# capacitive_switch.net
KiCad netlist of a schematic drawn in EAGLE
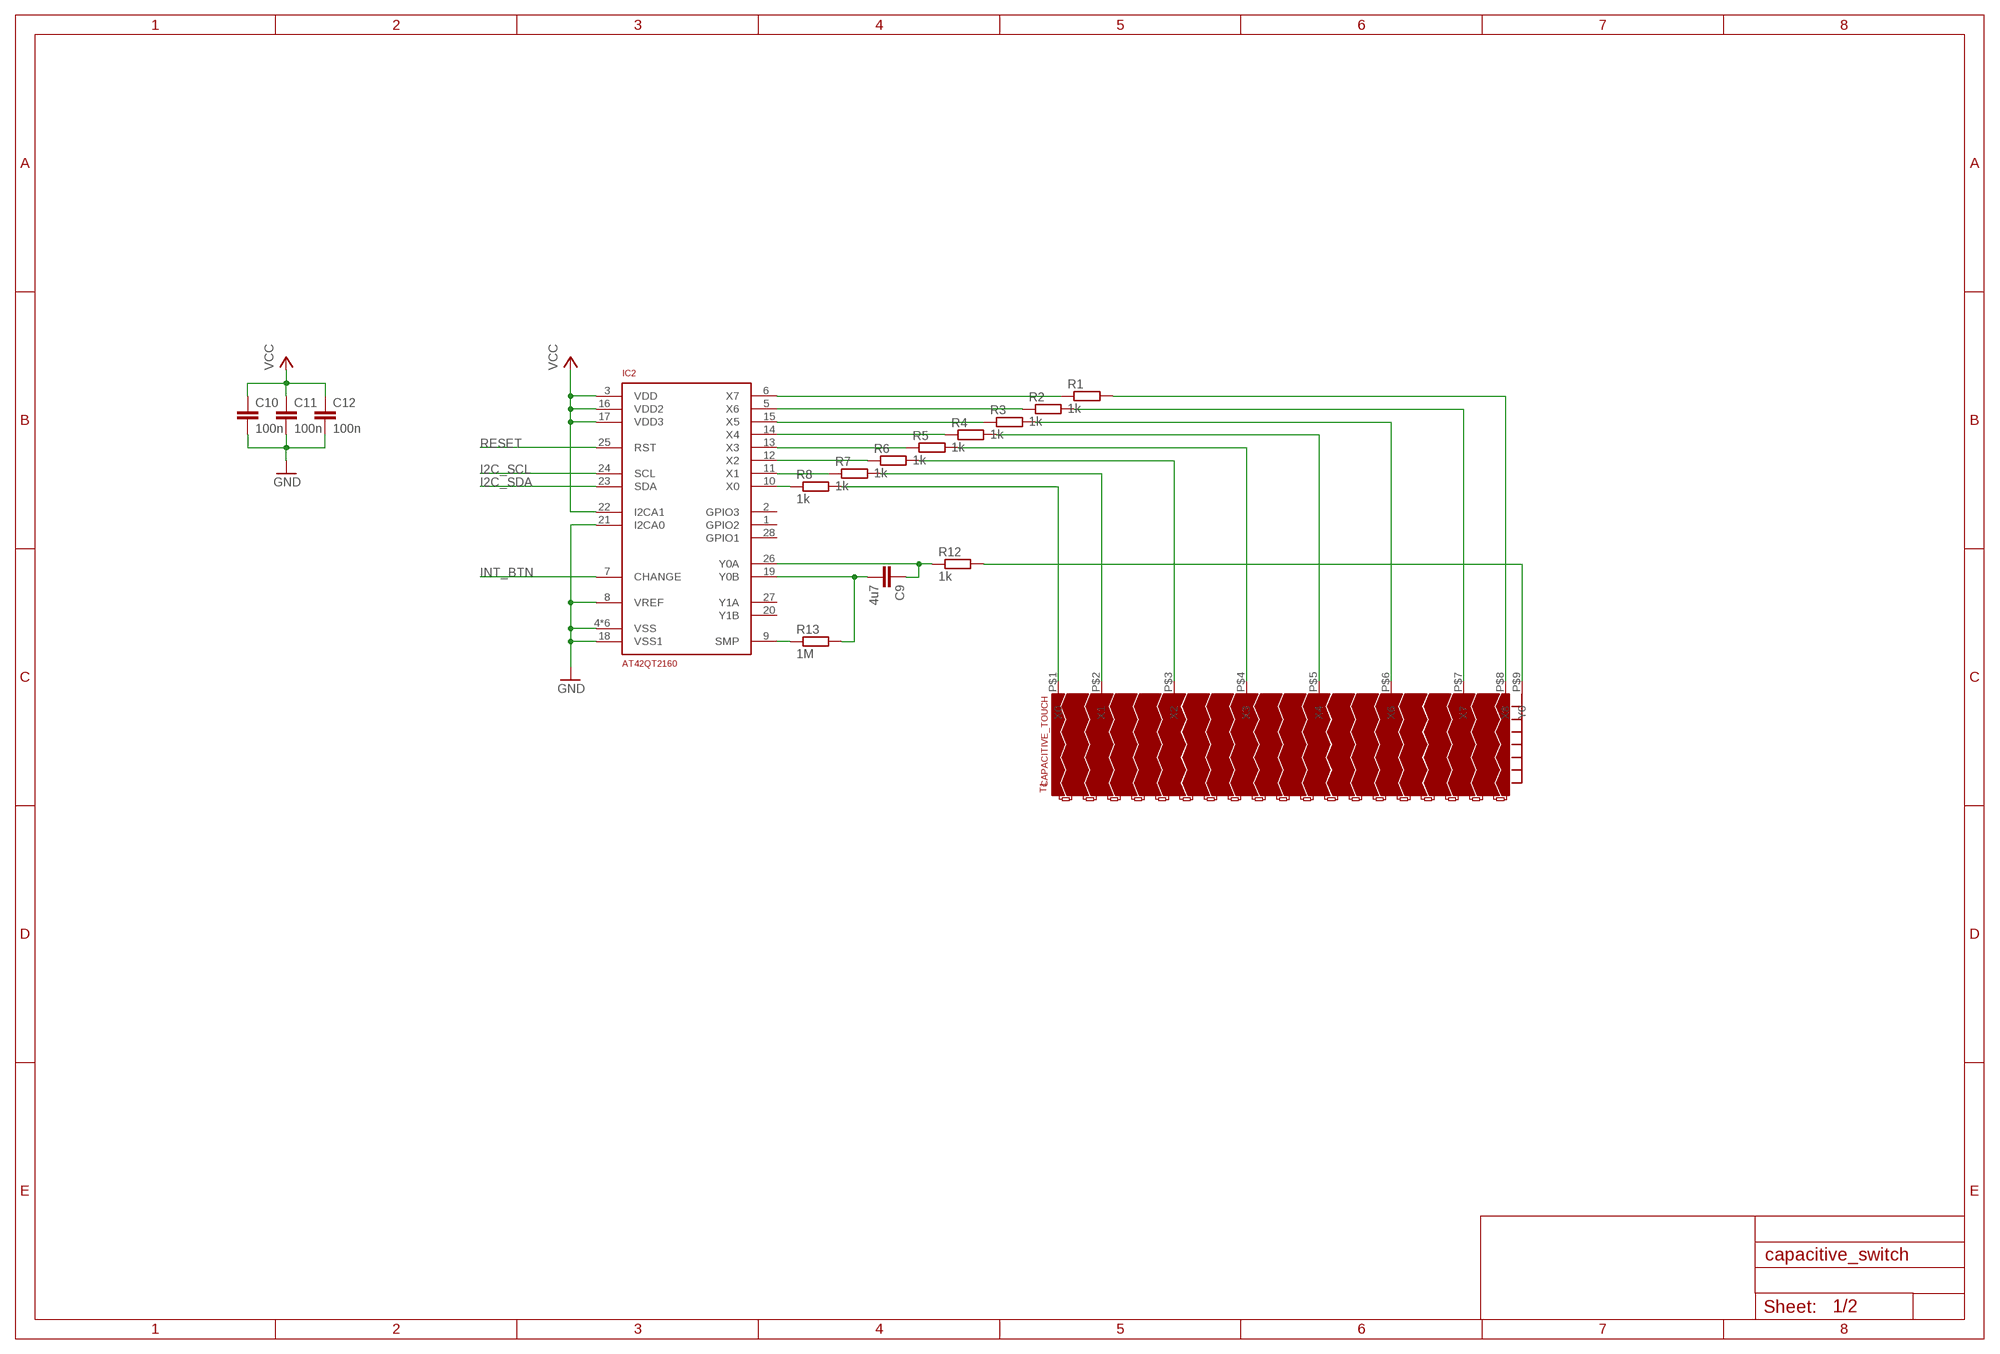
[diagram p0: schematic, sheet 1]
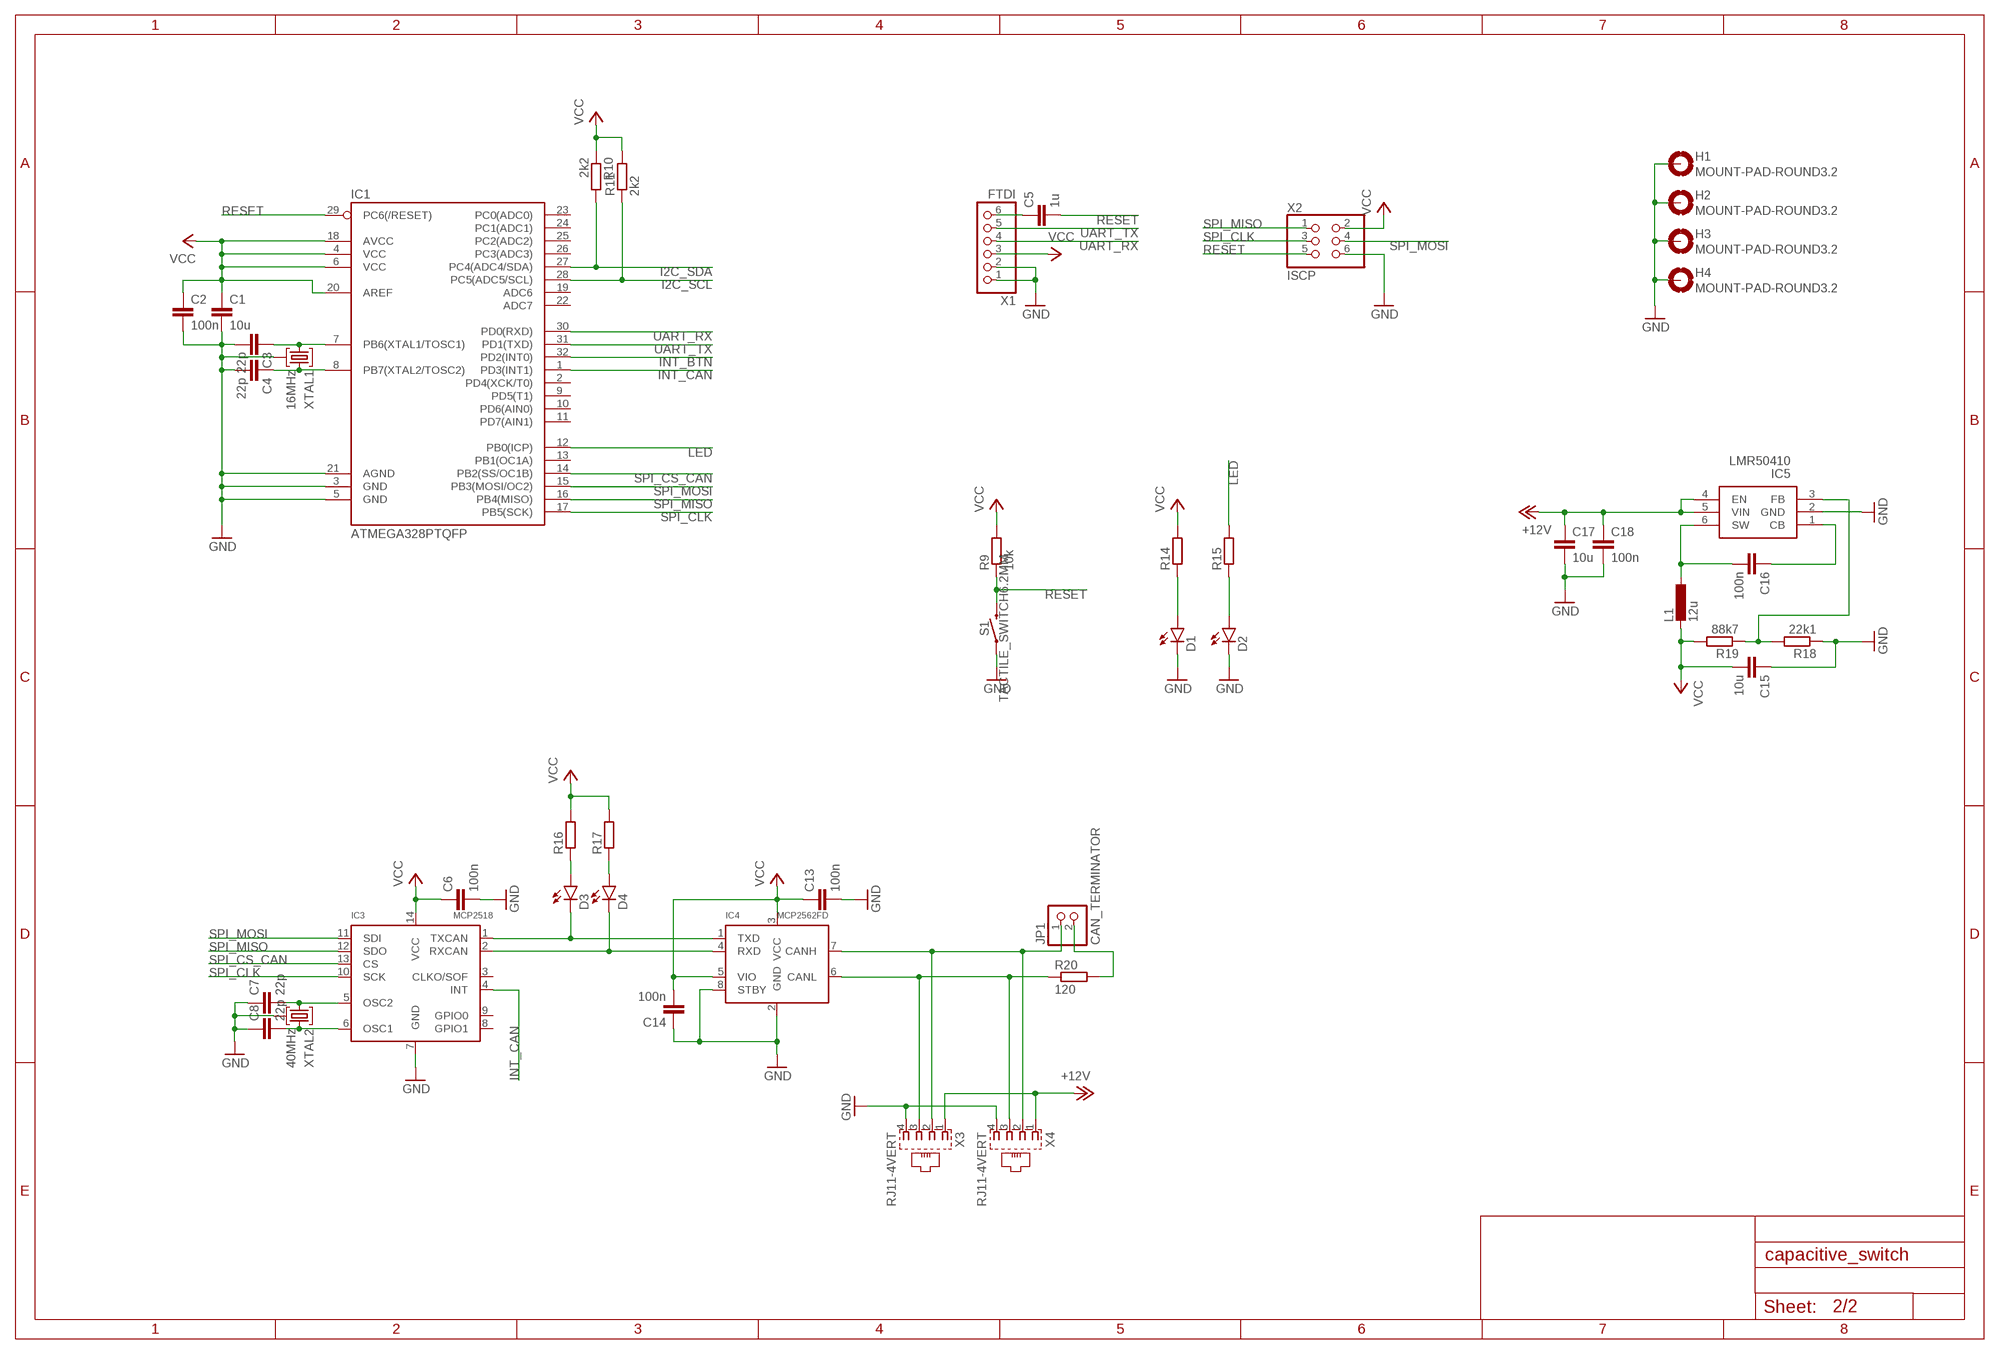
[diagram p1: schematic, sheet 2]

(export (version "E")
  (design (tool "Eeschema 10.0.6"))
  (components
    (comp (ref "C1")
      (value "10u")
      (footprint "eagle-import:C1206")
      (libsource (lib "eagle-import") (part "CAPACITOR1206"))
    )
    (comp (ref "C2")
      (value "100n")
      (footprint "eagle-import:C0805")
      (libsource (lib "eagle-import") (part "CAPACITOR0805"))
    )
    (comp (ref "C3")
      (value "22p")
      (footprint "eagle-import:C0805")
      (libsource (lib "eagle-import") (part "CAPACITOR0805"))
    )
    (comp (ref "C4")
      (value "22p")
      (footprint "eagle-import:C0805")
      (libsource (lib "eagle-import") (part "CAPACITOR0805"))
    )
    (comp (ref "C5")
      (value "1u")
      (footprint "eagle-import:C0805")
      (libsource (lib "eagle-import") (part "CAPACITOR0805"))
    )
    (comp (ref "C6")
      (value "100n")
      (footprint "eagle-import:C0805")
      (libsource (lib "eagle-import") (part "CAPACITOR0805"))
    )
    (comp (ref "C7")
      (value "22p")
      (footprint "eagle-import:C0805")
      (libsource (lib "eagle-import") (part "CAPACITOR0805"))
    )
    (comp (ref "C8")
      (value "22p")
      (footprint "eagle-import:C0805")
      (libsource (lib "eagle-import") (part "CAPACITOR0805"))
    )
    (comp (ref "C13")
      (value "100n")
      (footprint "eagle-import:C0805")
      (libsource (lib "eagle-import") (part "CAPACITOR0805"))
    )
    (comp (ref "C14")
      (value "100n")
      (footprint "eagle-import:C0805")
      (libsource (lib "eagle-import") (part "CAPACITOR0805"))
    )
    (comp (ref "C15")
      (value "10u")
      (footprint "eagle-import:C1206")
      (libsource (lib "eagle-import") (part "CAPACITOR1206"))
    )
    (comp (ref "C16")
      (value "100n")
      (footprint "eagle-import:C0805")
      (libsource (lib "eagle-import") (part "CAPACITOR0805"))
    )
    (comp (ref "C17")
      (value "10u")
      (footprint "eagle-import:C1206")
      (libsource (lib "eagle-import") (part "CAPACITOR1206"))
    )
    (comp (ref "C18")
      (value "100n")
      (footprint "eagle-import:C0805")
      (libsource (lib "eagle-import") (part "CAPACITOR0805"))
    )
    (comp (ref "D1")
      (value "LED1206")
      (footprint "eagle-import:CHIPLED_1206")
      (libsource (lib "eagle-import") (part "LED1206"))
    )
    (comp (ref "D2")
      (value "LED1206")
      (footprint "eagle-import:CHIPLED_1206")
      (libsource (lib "eagle-import") (part "LED1206"))
    )
    (comp (ref "D3")
      (value "LED1206")
      (footprint "eagle-import:CHIPLED_1206")
      (libsource (lib "eagle-import") (part "LED1206"))
    )
    (comp (ref "D4")
      (value "LED1206")
      (footprint "eagle-import:CHIPLED_1206")
      (libsource (lib "eagle-import") (part "LED1206"))
    )
    (comp (ref "H1")
      (value "MOUNT-PAD-ROUND3.2")
      (footprint "eagle-import:3,2-PAD")
      (libsource (lib "eagle-import") (part "MOUNT-PAD-ROUND3.2"))
    )
    (comp (ref "H2")
      (value "MOUNT-PAD-ROUND3.2")
      (footprint "eagle-import:3,2-PAD")
      (libsource (lib "eagle-import") (part "MOUNT-PAD-ROUND3.2"))
    )
    (comp (ref "H3")
      (value "MOUNT-PAD-ROUND3.2")
      (footprint "eagle-import:3,2-PAD")
      (libsource (lib "eagle-import") (part "MOUNT-PAD-ROUND3.2"))
    )
    (comp (ref "H4")
      (value "MOUNT-PAD-ROUND3.2")
      (footprint "eagle-import:3,2-PAD")
      (libsource (lib "eagle-import") (part "MOUNT-PAD-ROUND3.2"))
    )
    (comp (ref "IC1")
      (value "ATMEGA328PTQFP")
      (footprint "eagle-import:TQFP32_0.8MM_7X7MM")
      (libsource (lib "eagle-import") (part "ATMEGA328PTQFP"))
    )
    (comp (ref "IC3")
      (value "MCP2518")
      (footprint "eagle-import:SO14")
      (libsource (lib "eagle-import") (part "MCP2518FDSO14"))
    )
    (comp (ref "IC4")
      (value "MCP2562FD")
      (footprint "eagle-import:SO08")
      (libsource (lib "eagle-import") (part "MCP2562FDSO08"))
    )
    (comp (ref "IC5")
      (value "LMR50410")
      (footprint "eagle-import:SOT23-6")
      (libsource (lib "eagle-import") (part "LMR50410"))
    )
    (comp (ref "JP1")
      (value "CAN_TERMINATOR")
      (footprint "eagle-import:1X02")
      (libsource (lib "eagle-import") (part "PINHD-1X2"))
    )
    (comp (ref "L1")
      (value "12u")
      (footprint "eagle-import:L_7.3MM")
      (libsource (lib "eagle-import") (part "INDUCTOR7.3MM"))
    )
    (comp (ref "R9")
      (value "10k")
      (footprint "eagle-import:R0805")
      (libsource (lib "eagle-import") (part "RESISTOR0805"))
    )
    (comp (ref "R10")
      (value "2k2")
      (footprint "eagle-import:R0805")
      (libsource (lib "eagle-import") (part "RESISTOR0805"))
    )
    (comp (ref "R11")
      (value "2k2")
      (footprint "eagle-import:R0805")
      (libsource (lib "eagle-import") (part "RESISTOR0805"))
    )
    (comp (ref "R14")
      (value "RESISTOR0805")
      (footprint "eagle-import:R0805")
      (libsource (lib "eagle-import") (part "RESISTOR0805"))
    )
    (comp (ref "R15")
      (value "RESISTOR0805")
      (footprint "eagle-import:R0805")
      (libsource (lib "eagle-import") (part "RESISTOR0805"))
    )
    (comp (ref "R16")
      (value "RESISTOR0805")
      (footprint "eagle-import:R0805")
      (libsource (lib "eagle-import") (part "RESISTOR0805"))
    )
    (comp (ref "R17")
      (value "RESISTOR0805")
      (footprint "eagle-import:R0805")
      (libsource (lib "eagle-import") (part "RESISTOR0805"))
    )
    (comp (ref "R18")
      (value "22k1")
      (footprint "eagle-import:R0805")
      (libsource (lib "eagle-import") (part "RESISTOR0805"))
    )
    (comp (ref "R19")
      (value "88k7")
      (footprint "eagle-import:R0805")
      (libsource (lib "eagle-import") (part "RESISTOR0805"))
    )
    (comp (ref "R20")
      (value "120")
      (footprint "eagle-import:R0805")
      (libsource (lib "eagle-import") (part "RESISTOR0805"))
    )
    (comp (ref "S1")
      (value "TACTILE_SWITCH6.2MM")
      (footprint "eagle-import:TACTILE_SWITCH_SMD_6.2MM")
      (libsource (lib "eagle-import") (part "TACTILE_SWITCH6.2MM"))
    )
    (comp (ref "X1")
      (value "FTDI")
      (footprint "eagle-import:1X06")
      (libsource (lib "eagle-import") (part "PINHD-1X6"))
    )
    (comp (ref "X2")
      (value "ISCP")
      (footprint "eagle-import:2X03")
      (libsource (lib "eagle-import") (part "PINHD-2X3"))
    )
    (comp (ref "X3")
      (value "RJ11-4VERT")
      (footprint "eagle-import:RJ11-4_VERT")
      (libsource (lib "eagle-import") (part "RJ11-4VERT"))
    )
    (comp (ref "X4")
      (value "RJ11-4VERT")
      (footprint "eagle-import:RJ11-4_VERT")
      (libsource (lib "eagle-import") (part "RJ11-4VERT"))
    )
    (comp (ref "XTAL1")
      (value "16MHz")
      (footprint "eagle-import:XTAL_5.0X3.2_4")
      (libsource (lib "eagle-import") (part "CRYSTAL_GND5X3.2"))
    )
    (comp (ref "XTAL2")
      (value "40MHz")
      (footprint "eagle-import:XTAL_5.0X3.2_4")
      (libsource (lib "eagle-import") (part "CRYSTAL_GND5X3.2"))
    )
    (comp (ref "C9")
      (value "4u7")
      (footprint "eagle-import:C0805")
      (libsource (lib "eagle-import") (part "CAPACITOR0805"))
    )
    (comp (ref "C10")
      (value "100n")
      (footprint "eagle-import:C0805")
      (libsource (lib "eagle-import") (part "CAPACITOR0805"))
    )
    (comp (ref "C11")
      (value "100n")
      (footprint "eagle-import:C0805")
      (libsource (lib "eagle-import") (part "CAPACITOR0805"))
    )
    (comp (ref "C12")
      (value "100n")
      (footprint "eagle-import:C0805")
      (libsource (lib "eagle-import") (part "CAPACITOR0805"))
    )
    (comp (ref "IC2")
      (value "AT42QT2160")
      (footprint "eagle-import:QFN28_0.45MM_4X4MM")
      (libsource (lib "eagle-import") (part "AT42QT2160"))
    )
    (comp (ref "R1")
      (value "1k")
      (footprint "eagle-import:R0805")
      (libsource (lib "eagle-import") (part "RESISTOR0805"))
    )
    (comp (ref "R2")
      (value "1k")
      (footprint "eagle-import:R0805")
      (libsource (lib "eagle-import") (part "RESISTOR0805"))
    )
    (comp (ref "R3")
      (value "1k")
      (footprint "eagle-import:R0805")
      (libsource (lib "eagle-import") (part "RESISTOR0805"))
    )
    (comp (ref "R4")
      (value "1k")
      (footprint "eagle-import:R0805")
      (libsource (lib "eagle-import") (part "RESISTOR0805"))
    )
    (comp (ref "R5")
      (value "1k")
      (footprint "eagle-import:R0805")
      (libsource (lib "eagle-import") (part "RESISTOR0805"))
    )
    (comp (ref "R6")
      (value "1k")
      (footprint "eagle-import:R0805")
      (libsource (lib "eagle-import") (part "RESISTOR0805"))
    )
    (comp (ref "R7")
      (value "1k")
      (footprint "eagle-import:R0805")
      (libsource (lib "eagle-import") (part "RESISTOR0805"))
    )
    (comp (ref "R8")
      (value "1k")
      (footprint "eagle-import:R0805")
      (libsource (lib "eagle-import") (part "RESISTOR0805"))
    )
    (comp (ref "R12")
      (value "1k")
      (footprint "eagle-import:R0805")
      (libsource (lib "eagle-import") (part "RESISTOR0805"))
    )
    (comp (ref "R13")
      (value "1M")
      (footprint "eagle-import:R0805")
      (libsource (lib "eagle-import") (part "RESISTOR0805"))
    )
    (comp (ref "T1")
      (value "CAPACITIVE_TOUCH")
      (footprint "eagle-import:90X20_CAPACITIVE_TOUCH")
      (libsource (lib "eagle-import") (part "CAPACITIVE_TOUCH"))
    )
  )
  (nets
    (net (code "1") (name "+12V") (class "Default")
      (node (ref "C17") (pin "1") (pinfunction "1_1") (pintype "passive"))
      (node (ref "C18") (pin "1") (pinfunction "1_1") (pintype "passive"))
      (node (ref "IC5") (pin "4") (pinfunction "EN_4") (pintype "bidirectional"))
      (node (ref "IC5") (pin "5") (pinfunction "VIN_5") (pintype "bidirectional"))
      (node (ref "X3") (pin "1") (pinfunction "1_1") (pintype "passive"))
      (node (ref "X4") (pin "1") (pinfunction "1_1") (pintype "passive"))
    )
    (net (code "2") (name "GND") (class "Default")
      (node (ref "C1") (pin "2") (pinfunction "2_2") (pintype "passive"))
      (node (ref "C10") (pin "2") (pinfunction "2_2") (pintype "passive"))
      (node (ref "C11") (pin "2") (pinfunction "2_2") (pintype "passive"))
      (node (ref "C12") (pin "2") (pinfunction "2_2") (pintype "passive"))
      (node (ref "C13") (pin "2") (pinfunction "2_2") (pintype "passive"))
      (node (ref "C14") (pin "1") (pinfunction "1_1") (pintype "passive"))
      (node (ref "C15") (pin "1") (pinfunction "1_1") (pintype "passive"))
      (node (ref "C17") (pin "2") (pinfunction "2_2") (pintype "passive"))
      (node (ref "C18") (pin "2") (pinfunction "2_2") (pintype "passive"))
      (node (ref "C2") (pin "2") (pinfunction "2_2") (pintype "passive"))
      (node (ref "C3") (pin "2") (pinfunction "2_2") (pintype "passive"))
      (node (ref "C4") (pin "2") (pinfunction "2_2") (pintype "passive"))
      (node (ref "C6") (pin "2") (pinfunction "2_2") (pintype "passive"))
      (node (ref "C7") (pin "1") (pinfunction "1_1") (pintype "passive"))
      (node (ref "C8") (pin "1") (pinfunction "1_1") (pintype "passive"))
      (node (ref "D1") (pin "C") (pinfunction "C_C") (pintype "passive"))
      (node (ref "D2") (pin "C") (pinfunction "C_C") (pintype "passive"))
      (node (ref "H1") (pin "B3,2") (pinfunction "MOUNT_B3,2") (pintype "passive"))
      (node (ref "H1") (pin "P$1") (pinfunction "MOUNT_P$1") (pintype "passive"))
      (node (ref "H1") (pin "P$2") (pinfunction "MOUNT_P$2") (pintype "passive"))
      (node (ref "H1") (pin "P$3") (pinfunction "MOUNT_P$3") (pintype "passive"))
      (node (ref "H1") (pin "P$4") (pinfunction "MOUNT_P$4") (pintype "passive"))
      (node (ref "H1") (pin "P$5") (pinfunction "MOUNT_P$5") (pintype "passive"))
      (node (ref "H1") (pin "P$6") (pinfunction "MOUNT_P$6") (pintype "passive"))
      (node (ref "H1") (pin "P$7") (pinfunction "MOUNT_P$7") (pintype "passive"))
      (node (ref "H1") (pin "P$8") (pinfunction "MOUNT_P$8") (pintype "passive"))
      (node (ref "H2") (pin "B3,2") (pinfunction "MOUNT_B3,2") (pintype "passive"))
      (node (ref "H2") (pin "P$1") (pinfunction "MOUNT_P$1") (pintype "passive"))
      (node (ref "H2") (pin "P$2") (pinfunction "MOUNT_P$2") (pintype "passive"))
      (node (ref "H2") (pin "P$3") (pinfunction "MOUNT_P$3") (pintype "passive"))
      (node (ref "H2") (pin "P$4") (pinfunction "MOUNT_P$4") (pintype "passive"))
      (node (ref "H2") (pin "P$5") (pinfunction "MOUNT_P$5") (pintype "passive"))
      (node (ref "H2") (pin "P$6") (pinfunction "MOUNT_P$6") (pintype "passive"))
      (node (ref "H2") (pin "P$7") (pinfunction "MOUNT_P$7") (pintype "passive"))
      (node (ref "H2") (pin "P$8") (pinfunction "MOUNT_P$8") (pintype "passive"))
      (node (ref "H3") (pin "B3,2") (pinfunction "MOUNT_B3,2") (pintype "passive"))
      (node (ref "H3") (pin "P$1") (pinfunction "MOUNT_P$1") (pintype "passive"))
      (node (ref "H3") (pin "P$2") (pinfunction "MOUNT_P$2") (pintype "passive"))
      (node (ref "H3") (pin "P$3") (pinfunction "MOUNT_P$3") (pintype "passive"))
      (node (ref "H3") (pin "P$4") (pinfunction "MOUNT_P$4") (pintype "passive"))
      (node (ref "H3") (pin "P$5") (pinfunction "MOUNT_P$5") (pintype "passive"))
      (node (ref "H3") (pin "P$6") (pinfunction "MOUNT_P$6") (pintype "passive"))
      (node (ref "H3") (pin "P$7") (pinfunction "MOUNT_P$7") (pintype "passive"))
      (node (ref "H3") (pin "P$8") (pinfunction "MOUNT_P$8") (pintype "passive"))
      (node (ref "H4") (pin "B3,2") (pinfunction "MOUNT_B3,2") (pintype "passive"))
      (node (ref "H4") (pin "P$1") (pinfunction "MOUNT_P$1") (pintype "passive"))
      (node (ref "H4") (pin "P$2") (pinfunction "MOUNT_P$2") (pintype "passive"))
      (node (ref "H4") (pin "P$3") (pinfunction "MOUNT_P$3") (pintype "passive"))
      (node (ref "H4") (pin "P$4") (pinfunction "MOUNT_P$4") (pintype "passive"))
      (node (ref "H4") (pin "P$5") (pinfunction "MOUNT_P$5") (pintype "passive"))
      (node (ref "H4") (pin "P$6") (pinfunction "MOUNT_P$6") (pintype "passive"))
      (node (ref "H4") (pin "P$7") (pinfunction "MOUNT_P$7") (pintype "passive"))
      (node (ref "H4") (pin "P$8") (pinfunction "MOUNT_P$8") (pintype "passive"))
      (node (ref "IC1") (pin "21") (pinfunction "AGND_21") (pintype "bidirectional"))
      (node (ref "IC1") (pin "3") (pinfunction "GND_3") (pintype "bidirectional"))
      (node (ref "IC1") (pin "5") (pinfunction "GND_5") (pintype "bidirectional"))
      (node (ref "IC2") (pin "18") (pinfunction "VSS1_18") (pintype "bidirectional"))
      (node (ref "IC2") (pin "21") (pinfunction "I2CA0_21") (pintype "bidirectional"))
      (node (ref "IC2") (pin "29") (pinfunction "VSS_29") (pintype "bidirectional"))
      (node (ref "IC2") (pin "4") (pinfunction "VSS_4") (pintype "bidirectional"))
      (node (ref "IC2") (pin "8") (pinfunction "VREF_8") (pintype "bidirectional"))
      (node (ref "IC2") (pin "P$1") (pinfunction "VSS_P$1") (pintype "bidirectional"))
      (node (ref "IC2") (pin "P$2") (pinfunction "VSS_P$2") (pintype "bidirectional"))
      (node (ref "IC2") (pin "P$3") (pinfunction "VSS_P$3") (pintype "bidirectional"))
      (node (ref "IC2") (pin "P$4") (pinfunction "VSS_P$4") (pintype "bidirectional"))
      (node (ref "IC3") (pin "7") (pinfunction "GND_7") (pintype "bidirectional"))
      (node (ref "IC4") (pin "2") (pinfunction "GND_2") (pintype "bidirectional"))
      (node (ref "IC4") (pin "8") (pinfunction "STBY_8") (pintype "bidirectional"))
      (node (ref "IC5") (pin "2") (pinfunction "GND_2") (pintype "bidirectional"))
      (node (ref "R18") (pin "1") (pinfunction "1_1") (pintype "passive"))
      (node (ref "S1") (pin "A1") (pinfunction "1_A1") (pintype "passive"))
      (node (ref "S1") (pin "A2") (pinfunction "1_A2") (pintype "passive"))
      (node (ref "X1") (pin "1") (pinfunction "1_1") (pintype "passive"))
      (node (ref "X1") (pin "2") (pinfunction "2_2") (pintype "passive"))
      (node (ref "X2") (pin "6") (pinfunction "6_6") (pintype "passive"))
      (node (ref "X3") (pin "4") (pinfunction "4_4") (pintype "passive"))
      (node (ref "X4") (pin "4") (pinfunction "4_4") (pintype "passive"))
      (node (ref "XTAL1") (pin "2") (pinfunction "2_2") (pintype "passive"))
      (node (ref "XTAL1") (pin "4") (pinfunction "2_4") (pintype "passive"))
      (node (ref "XTAL2") (pin "2") (pinfunction "2_2") (pintype "passive"))
      (node (ref "XTAL2") (pin "4") (pinfunction "2_4") (pintype "passive"))
    )
    (net (code "3") (name "I2C_SCL") (class "Default")
      (node (ref "IC1") (pin "28") (pinfunction "PC5(ADC5/SCL)_28") (pintype "bidirectional"))
      (node (ref "IC2") (pin "24") (pinfunction "SCL_24") (pintype "bidirectional"))
      (node (ref "R11") (pin "1") (pinfunction "1_1") (pintype "passive"))
    )
    (net (code "4") (name "I2C_SDA") (class "Default")
      (node (ref "IC1") (pin "27") (pinfunction "PC4(ADC4/SDA)_27") (pintype "bidirectional"))
      (node (ref "IC2") (pin "23") (pinfunction "SDA_23") (pintype "bidirectional"))
      (node (ref "R10") (pin "2") (pinfunction "2_2") (pintype "passive"))
    )
    (net (code "5") (name "INT_BTN") (class "Default")
      (node (ref "IC1") (pin "32") (pinfunction "PD2(INT0)_32") (pintype "bidirectional"))
      (node (ref "IC2") (pin "7") (pinfunction "CHANGE_7") (pintype "bidirectional"))
    )
    (net (code "6") (name "INT_CAN") (class "Default")
      (node (ref "IC1") (pin "1") (pinfunction "PD3(INT1)_1") (pintype "bidirectional"))
      (node (ref "IC3") (pin "4") (pinfunction "INT_4") (pintype "bidirectional"))
    )
    (net (code "7") (name "LED") (class "Default")
      (node (ref "IC1") (pin "12") (pinfunction "PB0(ICP)_12") (pintype "bidirectional"))
      (node (ref "R15") (pin "2") (pinfunction "2_2") (pintype "passive"))
    )
    (net (code "8") (name "Net-(C5-Pad1)") (class "Default")
      (node (ref "C5") (pin "1") (pinfunction "1_1") (pintype "passive"))
      (node (ref "X1") (pin "6") (pinfunction "6_6") (pintype "passive"))
    )
    (net (code "9") (name "Net-(D1-PadA)") (class "Default")
      (node (ref "D1") (pin "A") (pinfunction "A_A") (pintype "passive"))
      (node (ref "R14") (pin "1") (pinfunction "1_1") (pintype "passive"))
    )
    (net (code "10") (name "Net-(D2-PadA)") (class "Default")
      (node (ref "D2") (pin "A") (pinfunction "A_A") (pintype "passive"))
      (node (ref "R15") (pin "1") (pinfunction "1_1") (pintype "passive"))
    )
    (net (code "11") (name "Net-(D3-PadA)") (class "Default")
      (node (ref "D3") (pin "A") (pinfunction "A_A") (pintype "passive"))
      (node (ref "R16") (pin "1") (pinfunction "1_1") (pintype "passive"))
    )
    (net (code "12") (name "Net-(D4-PadA)") (class "Default")
      (node (ref "D4") (pin "A") (pinfunction "A_A") (pintype "passive"))
      (node (ref "R17") (pin "1") (pinfunction "1_1") (pintype "passive"))
    )
    (net (code "13") (name "Net-(IC1-PB6(XTAL1{slash}TOSC1))") (class "Default")
      (node (ref "C3") (pin "1") (pinfunction "1_1") (pintype "passive"))
      (node (ref "IC1") (pin "7") (pinfunction "PB6(XTAL1/TOSC1)_7") (pintype "bidirectional"))
      (node (ref "XTAL1") (pin "1") (pinfunction "1_1") (pintype "passive"))
    )
    (net (code "14") (name "Net-(IC1-PB7(XTAL2{slash}TOSC2))") (class "Default")
      (node (ref "C4") (pin "1") (pinfunction "1_1") (pintype "passive"))
      (node (ref "IC1") (pin "8") (pinfunction "PB7(XTAL2/TOSC2)_8") (pintype "bidirectional"))
      (node (ref "XTAL1") (pin "3") (pinfunction "3_3") (pintype "passive"))
    )
    (net (code "15") (name "Net-(IC2-SMP)") (class "Default")
      (node (ref "IC2") (pin "9") (pinfunction "SMP_9") (pintype "bidirectional"))
      (node (ref "R13") (pin "1") (pinfunction "1_1") (pintype "passive"))
    )
    (net (code "16") (name "Net-(IC2-X0)") (class "Default")
      (node (ref "IC2") (pin "10") (pinfunction "X0_10") (pintype "bidirectional"))
      (node (ref "R8") (pin "1") (pinfunction "1_1") (pintype "passive"))
    )
    (net (code "17") (name "Net-(IC2-X1)") (class "Default")
      (node (ref "IC2") (pin "11") (pinfunction "X1_11") (pintype "bidirectional"))
      (node (ref "R7") (pin "1") (pinfunction "1_1") (pintype "passive"))
    )
    (net (code "18") (name "Net-(IC2-X2)") (class "Default")
      (node (ref "IC2") (pin "12") (pinfunction "X2_12") (pintype "bidirectional"))
      (node (ref "R6") (pin "1") (pinfunction "1_1") (pintype "passive"))
    )
    (net (code "19") (name "Net-(IC2-X3)") (class "Default")
      (node (ref "IC2") (pin "13") (pinfunction "X3_13") (pintype "bidirectional"))
      (node (ref "R5") (pin "1") (pinfunction "1_1") (pintype "passive"))
    )
    (net (code "20") (name "Net-(IC2-X4)") (class "Default")
      (node (ref "IC2") (pin "14") (pinfunction "X4_14") (pintype "bidirectional"))
      (node (ref "R4") (pin "1") (pinfunction "1_1") (pintype "passive"))
    )
    (net (code "21") (name "Net-(IC2-X5)") (class "Default")
      (node (ref "IC2") (pin "15") (pinfunction "X5_15") (pintype "bidirectional"))
      (node (ref "R3") (pin "1") (pinfunction "1_1") (pintype "passive"))
    )
    (net (code "22") (name "Net-(IC2-X6)") (class "Default")
      (node (ref "IC2") (pin "5") (pinfunction "X6_5") (pintype "bidirectional"))
      (node (ref "R2") (pin "1") (pinfunction "1_1") (pintype "passive"))
    )
    (net (code "23") (name "Net-(IC2-X7)") (class "Default")
      (node (ref "IC2") (pin "6") (pinfunction "X7_6") (pintype "bidirectional"))
      (node (ref "R1") (pin "1") (pinfunction "1_1") (pintype "passive"))
    )
    (net (code "24") (name "Net-(IC2-Y0A)") (class "Default")
      (node (ref "C9") (pin "1") (pinfunction "1_1") (pintype "passive"))
      (node (ref "IC2") (pin "26") (pinfunction "Y0A_26") (pintype "bidirectional"))
      (node (ref "R12") (pin "1") (pinfunction "1_1") (pintype "passive"))
    )
    (net (code "25") (name "Net-(IC2-Y0B)") (class "Default")
      (node (ref "C9") (pin "2") (pinfunction "2_2") (pintype "passive"))
      (node (ref "IC2") (pin "19") (pinfunction "Y0B_19") (pintype "bidirectional"))
      (node (ref "R13") (pin "2") (pinfunction "2_2") (pintype "passive"))
    )
    (net (code "26") (name "Net-(IC3-OSC1)") (class "Default")
      (node (ref "C8") (pin "2") (pinfunction "2_2") (pintype "passive"))
      (node (ref "IC3") (pin "6") (pinfunction "OSC1_6") (pintype "bidirectional"))
      (node (ref "XTAL2") (pin "3") (pinfunction "3_3") (pintype "passive"))
    )
    (net (code "27") (name "Net-(IC3-OSC2)") (class "Default")
      (node (ref "C7") (pin "2") (pinfunction "2_2") (pintype "passive"))
      (node (ref "IC3") (pin "5") (pinfunction "OSC2_5") (pintype "bidirectional"))
      (node (ref "XTAL2") (pin "1") (pinfunction "1_1") (pintype "passive"))
    )
    (net (code "28") (name "Net-(IC3-RXCAN)") (class "Default")
      (node (ref "D4") (pin "C") (pinfunction "C_C") (pintype "passive"))
      (node (ref "IC3") (pin "2") (pinfunction "RXCAN_2") (pintype "bidirectional"))
      (node (ref "IC4") (pin "4") (pinfunction "RXD_4") (pintype "bidirectional"))
    )
    (net (code "29") (name "Net-(IC3-TXCAN)") (class "Default")
      (node (ref "D3") (pin "C") (pinfunction "C_C") (pintype "passive"))
      (node (ref "IC3") (pin "1") (pinfunction "TXCAN_1") (pintype "bidirectional"))
      (node (ref "IC4") (pin "1") (pinfunction "TXD_1") (pintype "bidirectional"))
    )
    (net (code "30") (name "Net-(IC4-CANH)") (class "Default")
      (node (ref "IC4") (pin "7") (pinfunction "CANH_7") (pintype "bidirectional"))
      (node (ref "JP1") (pin "1") (pinfunction "1_1") (pintype "passive"))
      (node (ref "X3") (pin "2") (pinfunction "2_2") (pintype "passive"))
      (node (ref "X4") (pin "2") (pinfunction "2_2") (pintype "passive"))
    )
    (net (code "31") (name "Net-(IC4-CANL)") (class "Default")
      (node (ref "IC4") (pin "6") (pinfunction "CANL_6") (pintype "bidirectional"))
      (node (ref "R20") (pin "1") (pinfunction "1_1") (pintype "passive"))
      (node (ref "X3") (pin "3") (pinfunction "3_3") (pintype "passive"))
      (node (ref "X4") (pin "3") (pinfunction "3_3") (pintype "passive"))
    )
    (net (code "32") (name "Net-(IC5-CB)") (class "Default")
      (node (ref "C16") (pin "1") (pinfunction "1_1") (pintype "passive"))
      (node (ref "IC5") (pin "1") (pinfunction "CB_1") (pintype "bidirectional"))
    )
    (net (code "33") (name "Net-(IC5-FB)") (class "Default")
      (node (ref "IC5") (pin "3") (pinfunction "FB_3") (pintype "bidirectional"))
      (node (ref "R18") (pin "2") (pinfunction "2_2") (pintype "passive"))
      (node (ref "R19") (pin "1") (pinfunction "1_1") (pintype "passive"))
    )
    (net (code "34") (name "Net-(IC5-SW)") (class "Default")
      (node (ref "C16") (pin "2") (pinfunction "2_2") (pintype "passive"))
      (node (ref "IC5") (pin "6") (pinfunction "SW_6") (pintype "bidirectional"))
      (node (ref "L1") (pin "1") (pinfunction "1_1") (pintype "passive"))
    )
    (net (code "35") (name "Net-(JP1-Pad2)") (class "Default")
      (node (ref "JP1") (pin "2") (pinfunction "2_2") (pintype "passive"))
      (node (ref "R20") (pin "2") (pinfunction "2_2") (pintype "passive"))
    )
    (net (code "36") (name "Net-(T1-X0)") (class "Default")
      (node (ref "R8") (pin "2") (pinfunction "2_2") (pintype "passive"))
      (node (ref "T1") (pin "P$1") (pinfunction "X0_P$1") (pintype "bidirectional"))
    )
    (net (code "37") (name "Net-(T1-X1)") (class "Default")
      (node (ref "R7") (pin "2") (pinfunction "2_2") (pintype "passive"))
      (node (ref "T1") (pin "P$2") (pinfunction "X1_P$2") (pintype "bidirectional"))
    )
    (net (code "38") (name "Net-(T1-X2)") (class "Default")
      (node (ref "R6") (pin "2") (pinfunction "2_2") (pintype "passive"))
      (node (ref "T1") (pin "P$3") (pinfunction "X2_P$3") (pintype "bidirectional"))
    )
    (net (code "39") (name "Net-(T1-X3)") (class "Default")
      (node (ref "R5") (pin "2") (pinfunction "2_2") (pintype "passive"))
      (node (ref "T1") (pin "P$4") (pinfunction "X3_P$4") (pintype "bidirectional"))
    )
    (net (code "40") (name "Net-(T1-X4)") (class "Default")
      (node (ref "R4") (pin "2") (pinfunction "2_2") (pintype "passive"))
      (node (ref "T1") (pin "P$5") (pinfunction "X4_P$5") (pintype "bidirectional"))
    )
    (net (code "41") (name "Net-(T1-X6)") (class "Default")
      (node (ref "R3") (pin "2") (pinfunction "2_2") (pintype "passive"))
      (node (ref "T1") (pin "P$6") (pinfunction "X6_P$6") (pintype "bidirectional"))
    )
    (net (code "42") (name "Net-(T1-X7)") (class "Default")
      (node (ref "R2") (pin "2") (pinfunction "2_2") (pintype "passive"))
      (node (ref "T1") (pin "P$7") (pinfunction "X7_P$7") (pintype "bidirectional"))
    )
    (net (code "43") (name "Net-(T1-X8)") (class "Default")
      (node (ref "R1") (pin "2") (pinfunction "2_2") (pintype "passive"))
      (node (ref "T1") (pin "P$8") (pinfunction "X8_P$8") (pintype "bidirectional"))
    )
    (net (code "44") (name "Net-(T1-Y0)") (class "Default")
      (node (ref "R12") (pin "2") (pinfunction "2_2") (pintype "passive"))
      (node (ref "T1") (pin "P$9") (pinfunction "Y0_P$9") (pintype "bidirectional"))
    )
    (net (code "45") (name "RESET") (class "Default")
      (node (ref "C5") (pin "2") (pinfunction "2_2") (pintype "passive"))
      (node (ref "IC1") (pin "29") (pinfunction "PC6(/RESET)_29") (pintype "bidirectional"))
      (node (ref "IC2") (pin "25") (pinfunction "RST_25") (pintype "bidirectional"))
      (node (ref "R9") (pin "1") (pinfunction "1_1") (pintype "passive"))
      (node (ref "S1") (pin "B1") (pinfunction "2_B1") (pintype "passive"))
      (node (ref "S1") (pin "B2") (pinfunction "2_B2") (pintype "passive"))
      (node (ref "X2") (pin "5") (pinfunction "5_5") (pintype "passive"))
    )
    (net (code "46") (name "SPI_CLK") (class "Default")
      (node (ref "IC1") (pin "17") (pinfunction "PB5(SCK)_17") (pintype "bidirectional"))
      (node (ref "IC3") (pin "10") (pinfunction "SCK_10") (pintype "bidirectional"))
      (node (ref "X2") (pin "3") (pinfunction "3_3") (pintype "passive"))
    )
    (net (code "47") (name "SPI_CS_CAN") (class "Default")
      (node (ref "IC1") (pin "14") (pinfunction "PB2(SS/OC1B)_14") (pintype "bidirectional"))
      (node (ref "IC3") (pin "13") (pinfunction "CS_13") (pintype "bidirectional"))
    )
    (net (code "48") (name "SPI_MISO") (class "Default")
      (node (ref "IC1") (pin "16") (pinfunction "PB4(MISO)_16") (pintype "bidirectional"))
      (node (ref "IC3") (pin "12") (pinfunction "SDO_12") (pintype "bidirectional"))
      (node (ref "X2") (pin "1") (pinfunction "1_1") (pintype "passive"))
    )
    (net (code "49") (name "SPI_MOSI") (class "Default")
      (node (ref "IC1") (pin "15") (pinfunction "PB3(MOSI/OC2)_15") (pintype "bidirectional"))
      (node (ref "IC3") (pin "11") (pinfunction "SDI_11") (pintype "bidirectional"))
      (node (ref "X2") (pin "4") (pinfunction "4_4") (pintype "passive"))
    )
    (net (code "50") (name "UART_RX") (class "Default")
      (node (ref "IC1") (pin "30") (pinfunction "PD0(RXD)_30") (pintype "bidirectional"))
      (node (ref "X1") (pin "4") (pinfunction "4_4") (pintype "passive"))
    )
    (net (code "51") (name "UART_TX") (class "Default")
      (node (ref "IC1") (pin "31") (pinfunction "PD1(TXD)_31") (pintype "bidirectional"))
      (node (ref "X1") (pin "5") (pinfunction "5_5") (pintype "passive"))
    )
    (net (code "52") (name "VCC") (class "Default")
      (node (ref "C1") (pin "1") (pinfunction "1_1") (pintype "passive"))
      (node (ref "C10") (pin "1") (pinfunction "1_1") (pintype "passive"))
      (node (ref "C11") (pin "1") (pinfunction "1_1") (pintype "passive"))
      (node (ref "C12") (pin "1") (pinfunction "1_1") (pintype "passive"))
      (node (ref "C13") (pin "1") (pinfunction "1_1") (pintype "passive"))
      (node (ref "C14") (pin "2") (pinfunction "2_2") (pintype "passive"))
      (node (ref "C15") (pin "2") (pinfunction "2_2") (pintype "passive"))
      (node (ref "C2") (pin "1") (pinfunction "1_1") (pintype "passive"))
      (node (ref "C6") (pin "1") (pinfunction "1_1") (pintype "passive"))
      (node (ref "IC1") (pin "18") (pinfunction "AVCC_18") (pintype "bidirectional"))
      (node (ref "IC1") (pin "20") (pinfunction "AREF_20") (pintype "bidirectional"))
      (node (ref "IC1") (pin "4") (pinfunction "VCC_4") (pintype "bidirectional"))
      (node (ref "IC1") (pin "6") (pinfunction "VCC_6") (pintype "bidirectional"))
      (node (ref "IC2") (pin "16") (pinfunction "VDD2_16") (pintype "bidirectional"))
      (node (ref "IC2") (pin "17") (pinfunction "VDD3_17") (pintype "bidirectional"))
      (node (ref "IC2") (pin "22") (pinfunction "I2CA1_22") (pintype "bidirectional"))
      (node (ref "IC2") (pin "3") (pinfunction "VDD_3") (pintype "bidirectional"))
      (node (ref "IC3") (pin "14") (pinfunction "VCC_14") (pintype "bidirectional"))
      (node (ref "IC4") (pin "3") (pinfunction "VCC_3") (pintype "bidirectional"))
      (node (ref "IC4") (pin "5") (pinfunction "VIO_5") (pintype "bidirectional"))
      (node (ref "L1") (pin "2") (pinfunction "2_2") (pintype "passive"))
      (node (ref "R10") (pin "1") (pinfunction "1_1") (pintype "passive"))
      (node (ref "R11") (pin "2") (pinfunction "2_2") (pintype "passive"))
      (node (ref "R14") (pin "2") (pinfunction "2_2") (pintype "passive"))
      (node (ref "R16") (pin "2") (pinfunction "2_2") (pintype "passive"))
      (node (ref "R17") (pin "2") (pinfunction "2_2") (pintype "passive"))
      (node (ref "R19") (pin "2") (pinfunction "2_2") (pintype "passive"))
      (node (ref "R9") (pin "2") (pinfunction "2_2") (pintype "passive"))
      (node (ref "X1") (pin "3") (pinfunction "3_3") (pintype "passive"))
      (node (ref "X2") (pin "2") (pinfunction "2_2") (pintype "passive"))
    )
    (net (code "53") (name "unconnected-(IC1-ADC6-Pad19)") (class "Default")
      (node (ref "IC1") (pin "19") (pinfunction "ADC6_19") (pintype "bidirectional"))
    )
    (net (code "54") (name "unconnected-(IC1-ADC7-Pad22)") (class "Default")
      (node (ref "IC1") (pin "22") (pinfunction "ADC7_22") (pintype "bidirectional"))
    )
    (net (code "55") (name "unconnected-(IC1-PB1(OC1A)-Pad13)") (class "Default")
      (node (ref "IC1") (pin "13") (pinfunction "PB1(OC1A)_13") (pintype "bidirectional"))
    )
    (net (code "56") (name "unconnected-(IC1-PC0(ADC0)-Pad23)") (class "Default")
      (node (ref "IC1") (pin "23") (pinfunction "PC0(ADC0)_23") (pintype "bidirectional"))
    )
    (net (code "57") (name "unconnected-(IC1-PC1(ADC1)-Pad24)") (class "Default")
      (node (ref "IC1") (pin "24") (pinfunction "PC1(ADC1)_24") (pintype "bidirectional"))
    )
    (net (code "58") (name "unconnected-(IC1-PC2(ADC2)-Pad25)") (class "Default")
      (node (ref "IC1") (pin "25") (pinfunction "PC2(ADC2)_25") (pintype "bidirectional"))
    )
    (net (code "59") (name "unconnected-(IC1-PC3(ADC3)-Pad26)") (class "Default")
      (node (ref "IC1") (pin "26") (pinfunction "PC3(ADC3)_26") (pintype "bidirectional"))
    )
    (net (code "60") (name "unconnected-(IC1-PD4(XCK{slash}T0)-Pad2)") (class "Default")
      (node (ref "IC1") (pin "2") (pinfunction "PD4(XCK/T0)_2") (pintype "bidirectional"))
    )
    (net (code "61") (name "unconnected-(IC1-PD5(T1)-Pad9)") (class "Default")
      (node (ref "IC1") (pin "9") (pinfunction "PD5(T1)_9") (pintype "bidirectional"))
    )
    (net (code "62") (name "unconnected-(IC1-PD6(AIN0)-Pad10)") (class "Default")
      (node (ref "IC1") (pin "10") (pinfunction "PD6(AIN0)_10") (pintype "bidirectional"))
    )
    (net (code "63") (name "unconnected-(IC1-PD7(AIN1)-Pad11)") (class "Default")
      (node (ref "IC1") (pin "11") (pinfunction "PD7(AIN1)_11") (pintype "bidirectional"))
    )
    (net (code "64") (name "unconnected-(IC2-GPIO1-Pad28)") (class "Default")
      (node (ref "IC2") (pin "28") (pinfunction "GPIO1_28") (pintype "bidirectional"))
    )
    (net (code "65") (name "unconnected-(IC2-GPIO2-Pad1)") (class "Default")
      (node (ref "IC2") (pin "1") (pinfunction "GPIO2_1") (pintype "bidirectional"))
    )
    (net (code "66") (name "unconnected-(IC2-GPIO3-Pad2)") (class "Default")
      (node (ref "IC2") (pin "2") (pinfunction "GPIO3_2") (pintype "bidirectional"))
    )
    (net (code "67") (name "unconnected-(IC2-Y1A-Pad27)") (class "Default")
      (node (ref "IC2") (pin "27") (pinfunction "Y1A_27") (pintype "bidirectional"))
    )
    (net (code "68") (name "unconnected-(IC2-Y1B-Pad20)") (class "Default")
      (node (ref "IC2") (pin "20") (pinfunction "Y1B_20") (pintype "bidirectional"))
    )
    (net (code "69") (name "unconnected-(IC3-CLKO{slash}SOF-Pad3)") (class "Default")
      (node (ref "IC3") (pin "3") (pinfunction "CLKO/SOF_3") (pintype "bidirectional"))
    )
    (net (code "70") (name "unconnected-(IC3-GPIO0-Pad9)") (class "Default")
      (node (ref "IC3") (pin "9") (pinfunction "GPIO0_9") (pintype "bidirectional"))
    )
    (net (code "71") (name "unconnected-(IC3-GPIO1-Pad8)") (class "Default")
      (node (ref "IC3") (pin "8") (pinfunction "GPIO1_8") (pintype "bidirectional"))
    )
  )
)
